# schematic.net
KiCad netlist of a schematic drawn in EAGLE
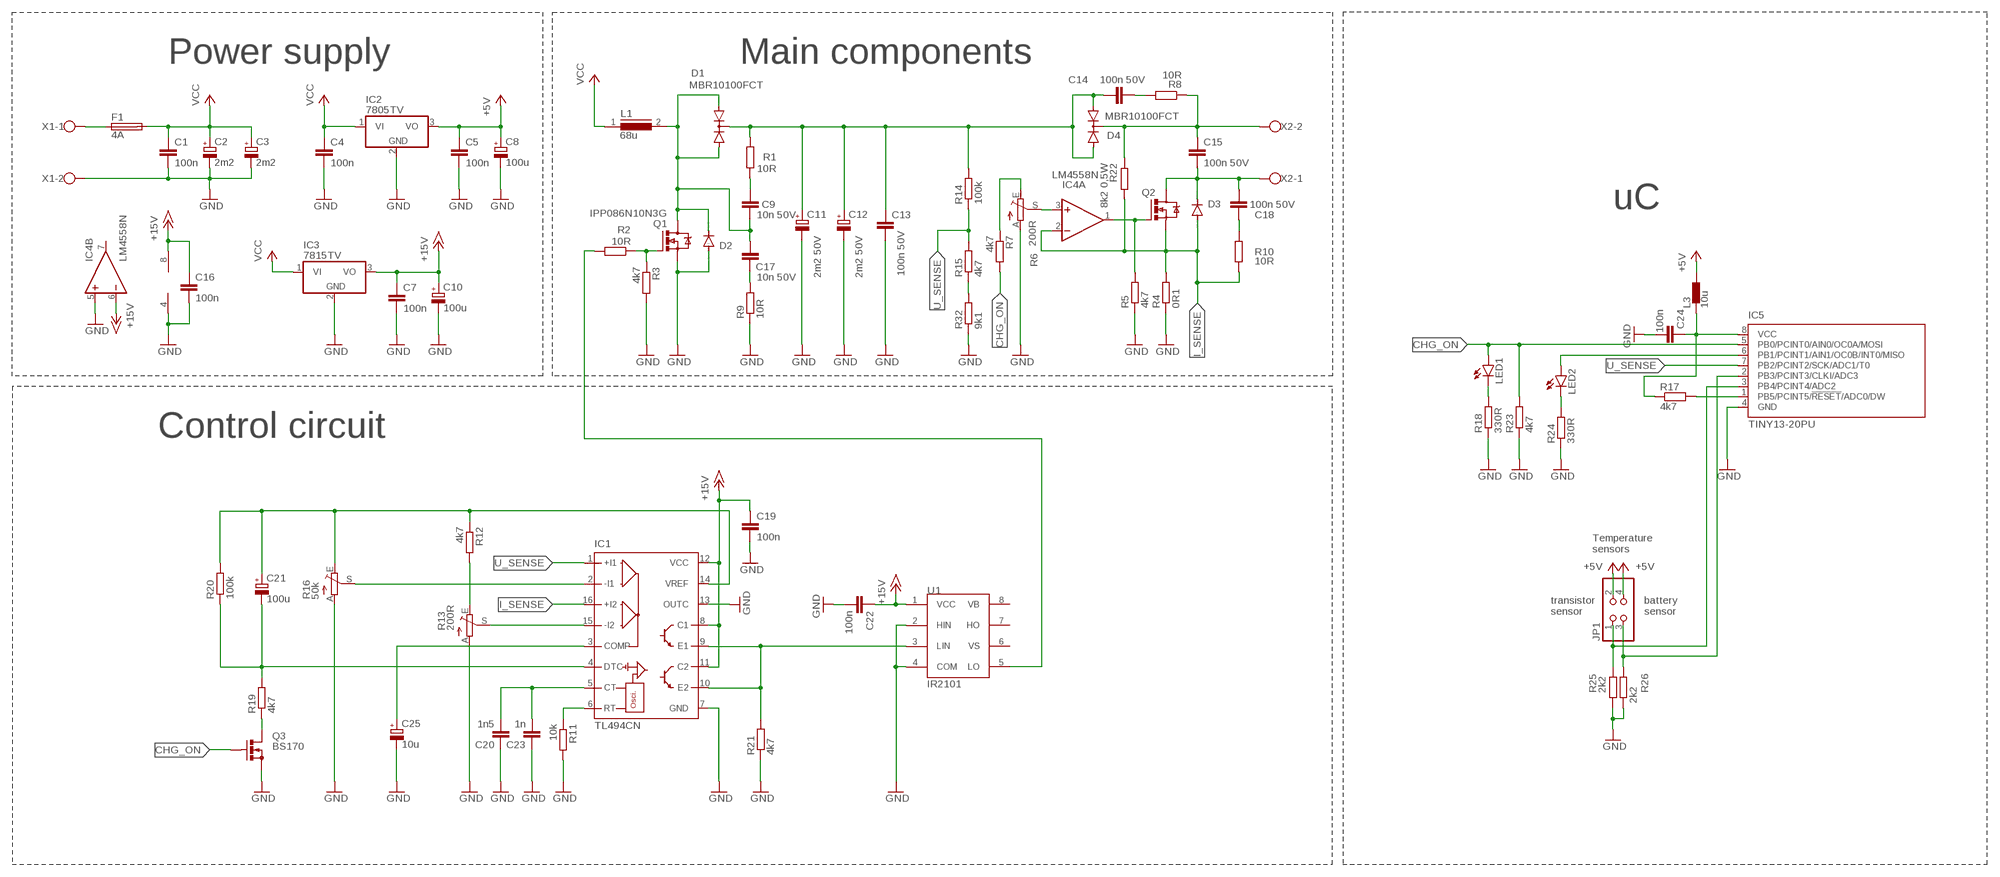
[diagram p0: schematic, sheet 1]

(export (version "E")
  (design (tool "Eeschema 10.0.6"))
  (components
    (comp (ref "C1")
      (value "100n")
      (footprint "eagle-import:C2.5-2")
      (libsource (lib "eagle-import") (part "C2.5/2"))
    )
    (comp (ref "C2")
      (value "2m2")
      (footprint "eagle-import:E7,5-16")
      (libsource (lib "eagle-import") (part "CPOL-EUE7.5-16"))
    )
    (comp (ref "C3")
      (value "2m2")
      (footprint "eagle-import:E7,5-16")
      (libsource (lib "eagle-import") (part "CPOL-EUE7.5-16"))
    )
    (comp (ref "C4")
      (value "100n")
      (footprint "eagle-import:C2.5-2")
      (libsource (lib "eagle-import") (part "C2.5/2"))
    )
    (comp (ref "C5")
      (value "100n")
      (footprint "eagle-import:C2.5-2")
      (libsource (lib "eagle-import") (part "C2.5/2"))
    )
    (comp (ref "C7")
      (value "100n")
      (footprint "eagle-import:C2.5-2")
      (libsource (lib "eagle-import") (part "C2.5/2"))
    )
    (comp (ref "C8")
      (value "100u")
      (footprint "eagle-import:E3,5-8")
      (libsource (lib "eagle-import") (part "CPOL-EUE3.5-8"))
    )
    (comp (ref "C9")
      (value "10n 50V")
      (footprint "eagle-import:C2.5-2")
      (libsource (lib "eagle-import") (part "C2.5/2"))
    )
    (comp (ref "C10")
      (value "100u")
      (footprint "eagle-import:E3,5-8")
      (libsource (lib "eagle-import") (part "CPOL-EUE3.5-8"))
    )
    (comp (ref "C11")
      (value "2m2 50V")
      (footprint "eagle-import:E7,5-18")
      (libsource (lib "eagle-import") (part "CPOL-EUE7.5-18"))
    )
    (comp (ref "C12")
      (value "2m2 50V")
      (footprint "eagle-import:E7,5-18")
      (libsource (lib "eagle-import") (part "CPOL-EUE7.5-18"))
    )
    (comp (ref "C13")
      (value "100n 50V")
      (footprint "eagle-import:C2.5-2")
      (libsource (lib "eagle-import") (part "C2.5/2"))
    )
    (comp (ref "C14")
      (value "100n 50V")
      (footprint "eagle-import:C2.5-2")
      (libsource (lib "eagle-import") (part "C2.5/2"))
    )
    (comp (ref "C15")
      (value "100n 50V")
      (footprint "eagle-import:C2.5-2")
      (libsource (lib "eagle-import") (part "C2.5/2"))
    )
    (comp (ref "C16")
      (value "100n")
      (footprint "eagle-import:C2.5-2")
      (libsource (lib "eagle-import") (part "C2.5/2"))
    )
    (comp (ref "C17")
      (value "10n 50V")
      (footprint "eagle-import:C2.5-2")
      (libsource (lib "eagle-import") (part "C2.5/2"))
    )
    (comp (ref "C18")
      (value "100n 50V")
      (footprint "eagle-import:C2.5-2")
      (libsource (lib "eagle-import") (part "C2.5/2"))
    )
    (comp (ref "C19")
      (value "100n")
      (footprint "eagle-import:C2.5-2")
      (libsource (lib "eagle-import") (part "C2.5/2"))
    )
    (comp (ref "C20")
      (value "1n5")
      (footprint "eagle-import:C2.5-2")
      (libsource (lib "eagle-import") (part "C2.5/2"))
    )
    (comp (ref "C21")
      (value "100u")
      (footprint "eagle-import:E3,5-8")
      (libsource (lib "eagle-import") (part "CPOL-EUE3.5-8"))
    )
    (comp (ref "C22")
      (value "100n")
      (footprint "eagle-import:C2.5-2")
      (libsource (lib "eagle-import") (part "C2.5/2"))
    )
    (comp (ref "C23")
      (value "1n")
      (footprint "eagle-import:C2.5-2")
      (libsource (lib "eagle-import") (part "C2.5/2"))
    )
    (comp (ref "C24")
      (value "100n")
      (footprint "eagle-import:C2.5-2")
      (libsource (lib "eagle-import") (part "C2.5/2"))
    )
    (comp (ref "C25")
      (value "10u")
      (footprint "eagle-import:E2,5-5")
      (libsource (lib "eagle-import") (part "CPOL-EUE2.5-5"))
    )
    (comp (ref "D1")
      (value "MBR10100FCT")
      (footprint "eagle-import:TO220ABS")
      (libsource (lib "eagle-import") (part "BYV32"))
    )
    (comp (ref "D2")
      (value "1N4933")
      (footprint "eagle-import:DO41-10")
      (libsource (lib "eagle-import") (part "1N4933"))
    )
    (comp (ref "D3")
      (value "1N4933")
      (footprint "eagle-import:DO41-10")
      (libsource (lib "eagle-import") (part "1N4933"))
    )
    (comp (ref "D4")
      (value "MBR10100FCT")
      (footprint "eagle-import:TO220ABS")
      (libsource (lib "eagle-import") (part "BYV32"))
    )
    (comp (ref "F1")
      (value "4A")
      (footprint "eagle-import:SH22")
      (libsource (lib "eagle-import") (part "SH22"))
    )
    (comp (ref "IC1")
      (value "TL494CN")
      (footprint "eagle-import:DIL16")
      (libsource (lib "eagle-import") (part "TL494NC"))
    )
    (comp (ref "IC2")
      (value "7805TV")
      (footprint "eagle-import:TO220V")
      (libsource (lib "eagle-import") (part "78TV05"))
    )
    (comp (ref "IC3")
      (value "7815TV")
      (footprint "eagle-import:TO220V")
      (libsource (lib "eagle-import") (part "78TV15"))
    )
    (comp (ref "IC4")
      (value "LM4558N")
      (footprint "eagle-import:DIL08")
      (libsource (lib "eagle-import") (part "4558NLM"))
    )
    (comp (ref "IC5")
      (value "TINY13-20PU")
      (footprint "eagle-import:DIL08")
      (fields (field (name "MPN") "ATTINY13-20PU"))
      (libsource (lib "eagle-import") (part "TINY13PU-20"))
    )
    (comp (ref "JP1")
      (value "PINHD-2X2")
      (footprint "eagle-import:2X02")
      (libsource (lib "eagle-import") (part "PINHD-2X2"))
    )
    (comp (ref "L1")
      (value "68u")
      (footprint "eagle-import:SFT1240")
      (libsource (lib "eagle-import") (part "SFT1240"))
    )
    (comp (ref "L3")
      (value "10u")
      (footprint "eagle-import:BL01RN1A")
      (libsource (lib "eagle-import") (part "BL01RN1A"))
    )
    (comp (ref "LED1")
      (value "LED5MM")
      (footprint "eagle-import:LED5MM")
      (libsource (lib "eagle-import") (part "LED5MM"))
    )
    (comp (ref "LED2")
      (value "LED5MM")
      (footprint "eagle-import:LED5MM")
      (libsource (lib "eagle-import") (part "LED5MM"))
    )
    (comp (ref "Q1")
      (value "IPP086N10N3G")
      (footprint "eagle-import:TO220BV")
      (libsource (lib "eagle-import") (part "IRF520"))
    )
    (comp (ref "Q2")
      (value "IRF520")
      (footprint "eagle-import:TO220BV")
      (libsource (lib "eagle-import") (part "IRF520"))
    )
    (comp (ref "Q3")
      (value "BS170")
      (footprint "eagle-import:SOT54E")
      (libsource (lib "eagle-import") (part "BS170"))
    )
    (comp (ref "R1")
      (value "10R")
      (footprint "eagle-import:0204_7")
      (libsource (lib "eagle-import") (part "R-EU_0204/7"))
    )
    (comp (ref "R2")
      (value "10R")
      (footprint "eagle-import:0204_7")
      (libsource (lib "eagle-import") (part "R-EU_0204/7"))
    )
    (comp (ref "R3")
      (value "4k7")
      (footprint "eagle-import:0204_7")
      (libsource (lib "eagle-import") (part "R-EU_0204/7"))
    )
    (comp (ref "R4")
      (value "0R1")
      (footprint "eagle-import:0204_5")
      (libsource (lib "eagle-import") (part "R-EU_0204/5"))
    )
    (comp (ref "R5")
      (value "4k7")
      (footprint "eagle-import:0204_7")
      (libsource (lib "eagle-import") (part "R-EU_0204/7"))
    )
    (comp (ref "R6")
      (value "200R")
      (footprint "eagle-import:B64Y")
      (libsource (lib "eagle-import") (part "TRIM_EU-B64Y"))
    )
    (comp (ref "R7")
      (value "4k7")
      (footprint "eagle-import:0204_7")
      (libsource (lib "eagle-import") (part "R-EU_0204/7"))
    )
    (comp (ref "R8")
      (value "10R")
      (footprint "eagle-import:0204_7")
      (libsource (lib "eagle-import") (part "R-EU_0204/7"))
    )
    (comp (ref "R9")
      (value "10R")
      (footprint "eagle-import:0204_7")
      (libsource (lib "eagle-import") (part "R-EU_0204/7"))
    )
    (comp (ref "R10")
      (value "10R")
      (footprint "eagle-import:0204_7")
      (libsource (lib "eagle-import") (part "R-EU_0204/7"))
    )
    (comp (ref "R11")
      (value "10k")
      (footprint "eagle-import:0204_7")
      (libsource (lib "eagle-import") (part "R-EU_0204/7"))
    )
    (comp (ref "R12")
      (value "4k7")
      (footprint "eagle-import:0204_7")
      (libsource (lib "eagle-import") (part "R-EU_0204/7"))
    )
    (comp (ref "R13")
      (value "200R")
      (footprint "eagle-import:B64Y")
      (libsource (lib "eagle-import") (part "TRIM_EU-B64Y"))
    )
    (comp (ref "R14")
      (value "100k")
      (footprint "eagle-import:0204_7")
      (libsource (lib "eagle-import") (part "R-EU_0204/7"))
    )
    (comp (ref "R15")
      (value "4k7")
      (footprint "eagle-import:0204_7")
      (libsource (lib "eagle-import") (part "R-EU_0204/7"))
    )
    (comp (ref "R16")
      (value "50k")
      (footprint "eagle-import:B64W")
      (libsource (lib "eagle-import") (part "TRIM_EU-B64W"))
    )
    (comp (ref "R17")
      (value "4k7")
      (footprint "eagle-import:0204_7")
      (libsource (lib "eagle-import") (part "R-EU_0204/7"))
    )
    (comp (ref "R18")
      (value "330R")
      (footprint "eagle-import:0204_7")
      (libsource (lib "eagle-import") (part "R-EU_0204/7"))
    )
    (comp (ref "R19")
      (value "4k7")
      (footprint "eagle-import:0204_7")
      (libsource (lib "eagle-import") (part "R-EU_0204/7"))
    )
    (comp (ref "R20")
      (value "100k")
      (footprint "eagle-import:0204_7")
      (libsource (lib "eagle-import") (part "R-EU_0204/7"))
    )
    (comp (ref "R21")
      (value "4k7")
      (footprint "eagle-import:0204_7")
      (libsource (lib "eagle-import") (part "R-EU_0204/7"))
    )
    (comp (ref "R22")
      (value "8k2 0,5W")
      (footprint "eagle-import:0204_7")
      (libsource (lib "eagle-import") (part "R-EU_0204/7"))
    )
    (comp (ref "R23")
      (value "4k7")
      (footprint "eagle-import:0204_7")
      (libsource (lib "eagle-import") (part "R-EU_0204/7"))
    )
    (comp (ref "R24")
      (value "330R")
      (footprint "eagle-import:0204_7")
      (libsource (lib "eagle-import") (part "R-EU_0204/7"))
    )
    (comp (ref "R25")
      (value "2k2")
      (footprint "eagle-import:0204_7")
      (libsource (lib "eagle-import") (part "R-EU_0204/7"))
    )
    (comp (ref "R26")
      (value "2k2")
      (footprint "eagle-import:0204_7")
      (libsource (lib "eagle-import") (part "R-EU_0204/7"))
    )
    (comp (ref "R32")
      (value "9k1")
      (footprint "eagle-import:0204_7")
      (libsource (lib "eagle-import") (part "R-EU_0204/7"))
    )
    (comp (ref "U1")
      (value "IR2101")
      (footprint "eagle-import:DIL08")
      (libsource (lib "eagle-import") (part "IR2101"))
    )
    (comp (ref "X1")
      (value "W237-102")
      (footprint "eagle-import:W237-102")
      (fields (field (name "MPN") "237-102"))
      (libsource (lib "eagle-import") (part "W237-102"))
    )
    (comp (ref "X2")
      (value "W237-102")
      (footprint "eagle-import:W237-102")
      (fields (field (name "MPN") "237-102"))
      (libsource (lib "eagle-import") (part "W237-102"))
    )
  )
  (nets
    (net (code "1") (name "+5V") (class "Default")
      (node (ref "C5") (pin "1") (pinfunction "1_1") (pintype "passive"))
      (node (ref "C8") (pin "+") (pinfunction "+_+") (pintype "passive"))
      (node (ref "IC2") (pin "3") (pinfunction "VO_3") (pintype "passive"))
      (node (ref "JP1") (pin "2") (pinfunction "2_2") (pintype "passive"))
      (node (ref "JP1") (pin "4") (pinfunction "4_4") (pintype "passive"))
      (node (ref "L3") (pin "2") (pinfunction "2_2") (pintype "passive"))
    )
    (net (code "2") (name "+15V") (class "Default")
      (node (ref "C10") (pin "+") (pinfunction "+_+") (pintype "passive"))
      (node (ref "C16") (pin "1") (pinfunction "1_1") (pintype "passive"))
      (node (ref "C19") (pin "1") (pinfunction "1_1") (pintype "passive"))
      (node (ref "C22") (pin "1") (pinfunction "1_1") (pintype "passive"))
      (node (ref "C7") (pin "1") (pinfunction "1_1") (pintype "passive"))
      (node (ref "IC1") (pin "11") (pinfunction "C2_11") (pintype "passive"))
      (node (ref "IC1") (pin "12") (pinfunction "VCC_12") (pintype "power_in"))
      (node (ref "IC1") (pin "8") (pinfunction "C1_8") (pintype "passive"))
      (node (ref "IC3") (pin "3") (pinfunction "VO_3") (pintype "passive"))
      (node (ref "IC4") (pin "6") (pinfunction "-IN_6") (pintype "input"))
      (node (ref "IC4") (pin "8") (pinfunction "V+_8") (pintype "power_in"))
      (node (ref "U1") (pin "1") (pinfunction "VCC_1") (pintype "power_in"))
    )
    (net (code "3") (name "/VB") (class "Default")
      (node (ref "U1") (pin "8") (pinfunction "VB_8") (pintype "power_in"))
    )
    (net (code "4") (name "CHG_ON") (class "Default")
      (node (ref "IC5") (pin "5") (pinfunction "PB0/PCINT0/AIN0/OC0A/MOSI_5") (pintype "bidirectional"))
      (node (ref "LED1") (pin "A") (pinfunction "A_A") (pintype "passive"))
      (node (ref "Q3") (pin "G") (pinfunction "G_G") (pintype "passive"))
      (node (ref "R23") (pin "2") (pinfunction "2_2") (pintype "passive"))
      (node (ref "R7") (pin "2") (pinfunction "2_2") (pintype "passive"))
    )
    (net (code "5") (name "GND") (class "Default")
      (node (ref "C1") (pin "2") (pinfunction "2_2") (pintype "passive"))
      (node (ref "C10") (pin "-") (pinfunction "-_-") (pintype "passive"))
      (node (ref "C11") (pin "-") (pinfunction "-_-") (pintype "passive"))
      (node (ref "C12") (pin "-") (pinfunction "-_-") (pintype "passive"))
      (node (ref "C13") (pin "2") (pinfunction "2_2") (pintype "passive"))
      (node (ref "C16") (pin "2") (pinfunction "2_2") (pintype "passive"))
      (node (ref "C19") (pin "2") (pinfunction "2_2") (pintype "passive"))
      (node (ref "C2") (pin "-") (pinfunction "-_-") (pintype "passive"))
      (node (ref "C20") (pin "1") (pinfunction "1_1") (pintype "passive"))
      (node (ref "C22") (pin "2") (pinfunction "2_2") (pintype "passive"))
      (node (ref "C23") (pin "1") (pinfunction "1_1") (pintype "passive"))
      (node (ref "C24") (pin "2") (pinfunction "2_2") (pintype "passive"))
      (node (ref "C25") (pin "-") (pinfunction "-_-") (pintype "passive"))
      (node (ref "C3") (pin "-") (pinfunction "-_-") (pintype "passive"))
      (node (ref "C4") (pin "2") (pinfunction "2_2") (pintype "passive"))
      (node (ref "C5") (pin "2") (pinfunction "2_2") (pintype "passive"))
      (node (ref "C7") (pin "2") (pinfunction "2_2") (pintype "passive"))
      (node (ref "C8") (pin "-") (pinfunction "-_-") (pintype "passive"))
      (node (ref "D2") (pin "A") (pinfunction "A_A") (pintype "passive"))
      (node (ref "IC1") (pin "13") (pinfunction "OUTC_13") (pintype "output"))
      (node (ref "IC1") (pin "7") (pinfunction "GND_7") (pintype "power_in"))
      (node (ref "IC2") (pin "2") (pinfunction "GND_2") (pintype "passive"))
      (node (ref "IC3") (pin "2") (pinfunction "GND_2") (pintype "passive"))
      (node (ref "IC4") (pin "4") (pinfunction "V-_4") (pintype "power_in"))
      (node (ref "IC4") (pin "5") (pinfunction "+IN_5") (pintype "input"))
      (node (ref "IC5") (pin "4") (pinfunction "GND_4") (pintype "power_in"))
      (node (ref "Q1") (pin "S") (pinfunction "S_S") (pintype "passive"))
      (node (ref "Q3") (pin "S") (pinfunction "S_S") (pintype "passive"))
      (node (ref "R11") (pin "2") (pinfunction "2_2") (pintype "passive"))
      (node (ref "R13") (pin "A") (pinfunction "A_A") (pintype "passive"))
      (node (ref "R16") (pin "A") (pinfunction "A_A") (pintype "passive"))
      (node (ref "R18") (pin "1") (pinfunction "1_1") (pintype "passive"))
      (node (ref "R21") (pin "1") (pinfunction "1_1") (pintype "passive"))
      (node (ref "R23") (pin "1") (pinfunction "1_1") (pintype "passive"))
      (node (ref "R24") (pin "1") (pinfunction "1_1") (pintype "passive"))
      (node (ref "R25") (pin "1") (pinfunction "1_1") (pintype "passive"))
      (node (ref "R26") (pin "1") (pinfunction "1_1") (pintype "passive"))
      (node (ref "R3") (pin "2") (pinfunction "2_2") (pintype "passive"))
      (node (ref "R32") (pin "1") (pinfunction "1_1") (pintype "passive"))
      (node (ref "R4") (pin "1") (pinfunction "1_1") (pintype "passive"))
      (node (ref "R5") (pin "1") (pinfunction "1_1") (pintype "passive"))
      (node (ref "R6") (pin "A") (pinfunction "A_A") (pintype "passive"))
      (node (ref "R9") (pin "1") (pinfunction "1_1") (pintype "passive"))
      (node (ref "U1") (pin "2") (pinfunction "HIN_2") (pintype "input"))
      (node (ref "U1") (pin "4") (pinfunction "COM_4") (pintype "power_in"))
      (node (ref "X1") (pin "2") (pinfunction "KL_2") (pintype "passive"))
    )
    (net (code "6") (name "I_SENSE") (class "Default")
      (node (ref "D3") (pin "A") (pinfunction "A_A") (pintype "passive"))
      (node (ref "IC1") (pin "16") (pinfunction "+I2_16") (pintype "input"))
      (node (ref "IC4") (pin "2") (pinfunction "-IN_2") (pintype "input"))
      (node (ref "Q2") (pin "S") (pinfunction "S_S") (pintype "passive"))
      (node (ref "R10") (pin "2") (pinfunction "2_2") (pintype "passive"))
      (node (ref "R22") (pin "2") (pinfunction "2_2") (pintype "passive"))
      (node (ref "R4") (pin "2") (pinfunction "2_2") (pintype "passive"))
    )
    (net (code "7") (name "Net-(C9-Pad1)") (class "Default")
      (node (ref "C9") (pin "1") (pinfunction "1_1") (pintype "passive"))
      (node (ref "R1") (pin "1") (pinfunction "1_1") (pintype "passive"))
    )
    (net (code "8") (name "Net-(C11-Pad+)") (class "Default")
      (node (ref "C11") (pin "+") (pinfunction "+_+") (pintype "passive"))
      (node (ref "C12") (pin "+") (pinfunction "+_+") (pintype "passive"))
      (node (ref "C13") (pin "1") (pinfunction "1_1") (pintype "passive"))
      (node (ref "C14") (pin "2") (pinfunction "2_2") (pintype "passive"))
      (node (ref "D1") (pin "C") (pinfunction "C_C") (pintype "passive"))
      (node (ref "D4") (pin "A1") (pinfunction "A1_A1") (pintype "passive"))
      (node (ref "D4") (pin "A2") (pinfunction "A2_A2") (pintype "passive"))
      (node (ref "R1") (pin "2") (pinfunction "2_2") (pintype "passive"))
      (node (ref "R14") (pin "2") (pinfunction "2_2") (pintype "passive"))
    )
    (net (code "9") (name "Net-(C14-Pad1)") (class "Default")
      (node (ref "C14") (pin "1") (pinfunction "1_1") (pintype "passive"))
      (node (ref "R8") (pin "2") (pinfunction "2_2") (pintype "passive"))
    )
    (net (code "10") (name "Net-(C17-Pad1)") (class "Default")
      (node (ref "C17") (pin "1") (pinfunction "1_1") (pintype "passive"))
      (node (ref "C9") (pin "2") (pinfunction "2_2") (pintype "passive"))
      (node (ref "D1") (pin "A1") (pinfunction "A1_A1") (pintype "passive"))
      (node (ref "D1") (pin "A2") (pinfunction "A2_A2") (pintype "passive"))
      (node (ref "D2") (pin "C") (pinfunction "C_C") (pintype "passive"))
      (node (ref "L1") (pin "2") (pinfunction "2_2") (pintype "passive"))
      (node (ref "Q1") (pin "D") (pinfunction "D_D") (pintype "passive"))
    )
    (net (code "11") (name "Net-(C17-Pad2)") (class "Default")
      (node (ref "C17") (pin "2") (pinfunction "2_2") (pintype "passive"))
      (node (ref "R9") (pin "2") (pinfunction "2_2") (pintype "passive"))
    )
    (net (code "12") (name "Net-(C18-Pad2)") (class "Default")
      (node (ref "C18") (pin "2") (pinfunction "2_2") (pintype "passive"))
      (node (ref "R10") (pin "1") (pinfunction "1_1") (pintype "passive"))
    )
    (net (code "13") (name "Net-(IC1--I1)") (class "Default")
      (node (ref "IC1") (pin "2") (pinfunction "-I1_2") (pintype "input"))
      (node (ref "R16") (pin "S") (pinfunction "S_S") (pintype "passive"))
    )
    (net (code "14") (name "Net-(IC1--I2)") (class "Default")
      (node (ref "IC1") (pin "15") (pinfunction "-I2_15") (pintype "input"))
      (node (ref "R13") (pin "S") (pinfunction "S_S") (pintype "passive"))
    )
    (net (code "15") (name "Net-(IC1-COMP)") (class "Default")
      (node (ref "C25") (pin "+") (pinfunction "+_+") (pintype "passive"))
      (node (ref "IC1") (pin "3") (pinfunction "COMP_3") (pintype "passive"))
    )
    (net (code "16") (name "Net-(IC1-CT)") (class "Default")
      (node (ref "C20") (pin "2") (pinfunction "2_2") (pintype "passive"))
      (node (ref "C23") (pin "2") (pinfunction "2_2") (pintype "passive"))
      (node (ref "IC1") (pin "5") (pinfunction "CT_5") (pintype "input"))
    )
    (net (code "17") (name "Net-(IC1-DTC)") (class "Default")
      (node (ref "C21") (pin "-") (pinfunction "-_-") (pintype "passive"))
      (node (ref "IC1") (pin "4") (pinfunction "DTC_4") (pintype "input"))
      (node (ref "R19") (pin "2") (pinfunction "2_2") (pintype "passive"))
      (node (ref "R20") (pin "1") (pinfunction "1_1") (pintype "passive"))
    )
    (net (code "18") (name "Net-(IC1-E1)") (class "Default")
      (node (ref "IC1") (pin "10") (pinfunction "E2_10") (pintype "passive"))
      (node (ref "IC1") (pin "9") (pinfunction "E1_9") (pintype "passive"))
      (node (ref "R21") (pin "2") (pinfunction "2_2") (pintype "passive"))
      (node (ref "U1") (pin "3") (pinfunction "LIN_3") (pintype "input"))
    )
    (net (code "19") (name "Net-(IC1-RT)") (class "Default")
      (node (ref "IC1") (pin "6") (pinfunction "RT_6") (pintype "input"))
      (node (ref "R11") (pin "1") (pinfunction "1_1") (pintype "passive"))
    )
    (net (code "20") (name "Net-(IC1-VREF)") (class "Default")
      (node (ref "C21") (pin "+") (pinfunction "+_+") (pintype "passive"))
      (node (ref "IC1") (pin "14") (pinfunction "VREF_14") (pintype "input"))
      (node (ref "R12") (pin "1") (pinfunction "1_1") (pintype "passive"))
      (node (ref "R16") (pin "E") (pinfunction "E_E") (pintype "passive"))
      (node (ref "R20") (pin "2") (pinfunction "2_2") (pintype "passive"))
    )
    (net (code "21") (name "Net-(IC4A-+IN)") (class "Default")
      (node (ref "IC4") (pin "3") (pinfunction "+IN_3") (pintype "input"))
      (node (ref "R6") (pin "S") (pinfunction "S_S") (pintype "passive"))
    )
    (net (code "22") (name "Net-(IC4A-OUT)") (class "Default")
      (node (ref "IC4") (pin "1") (pinfunction "OUT_1") (pintype "output"))
      (node (ref "Q2") (pin "G") (pinfunction "G_G") (pintype "passive"))
      (node (ref "R5") (pin "2") (pinfunction "2_2") (pintype "passive"))
    )
    (net (code "23") (name "Net-(IC5-PB1{slash}PCINT1{slash}AIN1{slash}OC0B{slash}INT0{slash}MISO)") (class "Default")
      (node (ref "IC5") (pin "6") (pinfunction "PB1/PCINT1/AIN1/OC0B/INT0/MISO_6") (pintype "bidirectional"))
      (node (ref "LED2") (pin "A") (pinfunction "A_A") (pintype "passive"))
    )
    (net (code "24") (name "Net-(IC5-PB3{slash}PCINT3{slash}CLKI{slash}ADC3)") (class "Default")
      (node (ref "IC5") (pin "2") (pinfunction "PB3/PCINT3/CLKI/ADC3_2") (pintype "bidirectional"))
      (node (ref "JP1") (pin "3") (pinfunction "3_3") (pintype "passive"))
      (node (ref "R26") (pin "2") (pinfunction "2_2") (pintype "passive"))
    )
    (net (code "25") (name "Net-(IC5-PB4{slash}PCINT4{slash}ADC2)") (class "Default")
      (node (ref "IC5") (pin "3") (pinfunction "PB4/PCINT4/ADC2_3") (pintype "bidirectional"))
      (node (ref "JP1") (pin "1") (pinfunction "1_1") (pintype "passive"))
      (node (ref "R25") (pin "2") (pinfunction "2_2") (pintype "passive"))
    )
    (net (code "26") (name "Net-(IC5-PB5{slash}PCINT5{slash}~{RESET}{slash}ADC0{slash}DW)") (class "Default")
      (node (ref "IC5") (pin "1") (pinfunction "PB5/PCINT5/~{RESET}/ADC0/DW_1") (pintype "bidirectional"))
      (node (ref "R17") (pin "2") (pinfunction "2_2") (pintype "passive"))
    )
    (net (code "27") (name "Net-(IC5-VCC)") (class "Default")
      (node (ref "C24") (pin "1") (pinfunction "1_1") (pintype "passive"))
      (node (ref "IC5") (pin "8") (pinfunction "VCC_8") (pintype "power_in"))
      (node (ref "L3") (pin "1") (pinfunction "1_1") (pintype "passive"))
      (node (ref "R17") (pin "1") (pinfunction "1_1") (pintype "passive"))
    )
    (net (code "28") (name "Net-(LED1-C)") (class "Default")
      (node (ref "LED1") (pin "K") (pinfunction "C_K") (pintype "passive"))
      (node (ref "R18") (pin "2") (pinfunction "2_2") (pintype "passive"))
    )
    (net (code "29") (name "Net-(LED2-C)") (class "Default")
      (node (ref "LED2") (pin "K") (pinfunction "C_K") (pintype "passive"))
      (node (ref "R24") (pin "2") (pinfunction "2_2") (pintype "passive"))
    )
    (net (code "30") (name "Net-(Q1-PadG)") (class "Default")
      (node (ref "Q1") (pin "G") (pinfunction "G_G") (pintype "passive"))
      (node (ref "R2") (pin "1") (pinfunction "1_1") (pintype "passive"))
      (node (ref "R3") (pin "1") (pinfunction "1_1") (pintype "passive"))
    )
    (net (code "31") (name "Net-(Q3-PadD)") (class "Default")
      (node (ref "Q3") (pin "D") (pinfunction "D_D") (pintype "passive"))
      (node (ref "R19") (pin "1") (pinfunction "1_1") (pintype "passive"))
    )
    (net (code "32") (name "Net-(R6-PadE)") (class "Default")
      (node (ref "R6") (pin "E") (pinfunction "E_E") (pintype "passive"))
      (node (ref "R7") (pin "1") (pinfunction "1_1") (pintype "passive"))
    )
    (net (code "33") (name "Net-(R12-Pad2)") (class "Default")
      (node (ref "R12") (pin "2") (pinfunction "2_2") (pintype "passive"))
      (node (ref "R13") (pin "E") (pinfunction "E_E") (pintype "passive"))
    )
    (net (code "34") (name "Net-(R15-Pad1)") (class "Default")
      (node (ref "R15") (pin "1") (pinfunction "1_1") (pintype "passive"))
      (node (ref "R32") (pin "2") (pinfunction "2_2") (pintype "passive"))
    )
    (net (code "35") (name "Net-(U1-LO)") (class "Default")
      (node (ref "R2") (pin "2") (pinfunction "2_2") (pintype "passive"))
      (node (ref "U1") (pin "5") (pinfunction "LO_5") (pintype "output"))
    )
    (net (code "36") (name "Net-(X1A-KL)") (class "Default")
      (node (ref "F1") (pin "1") (pinfunction "1_1") (pintype "passive"))
      (node (ref "X1") (pin "1") (pinfunction "KL_1") (pintype "passive"))
    )
    (net (code "37") (name "Net-(X2A-KL)") (class "Default")
      (node (ref "C15") (pin "2") (pinfunction "2_2") (pintype "passive"))
      (node (ref "C18") (pin "1") (pinfunction "1_1") (pintype "passive"))
      (node (ref "D3") (pin "C") (pinfunction "C_C") (pintype "passive"))
      (node (ref "Q2") (pin "D") (pinfunction "D_D") (pintype "passive"))
      (node (ref "X2") (pin "1") (pinfunction "KL_1") (pintype "passive"))
    )
    (net (code "38") (name "Net-(X2B-KL)") (class "Default")
      (node (ref "C15") (pin "1") (pinfunction "1_1") (pintype "passive"))
      (node (ref "D4") (pin "C") (pinfunction "C_C") (pintype "passive"))
      (node (ref "R22") (pin "1") (pinfunction "1_1") (pintype "passive"))
      (node (ref "R8") (pin "1") (pinfunction "1_1") (pintype "passive"))
      (node (ref "X2") (pin "2") (pinfunction "KL_2") (pintype "passive"))
    )
    (net (code "39") (name "U_SENSE") (class "Default")
      (node (ref "IC1") (pin "1") (pinfunction "+I1_1") (pintype "input"))
      (node (ref "IC5") (pin "7") (pinfunction "PB2/PCINT2/SCK/ADC1/T0_7") (pintype "bidirectional"))
      (node (ref "R14") (pin "1") (pinfunction "1_1") (pintype "passive"))
      (node (ref "R15") (pin "2") (pinfunction "2_2") (pintype "passive"))
    )
    (net (code "40") (name "VCC") (class "Default")
      (node (ref "C1") (pin "1") (pinfunction "1_1") (pintype "passive"))
      (node (ref "C2") (pin "+") (pinfunction "+_+") (pintype "passive"))
      (node (ref "C3") (pin "+") (pinfunction "+_+") (pintype "passive"))
      (node (ref "C4") (pin "1") (pinfunction "1_1") (pintype "passive"))
      (node (ref "F1") (pin "2") (pinfunction "2_2") (pintype "passive"))
      (node (ref "IC2") (pin "1") (pinfunction "VI_1") (pintype "input"))
      (node (ref "IC3") (pin "1") (pinfunction "VI_1") (pintype "input"))
      (node (ref "L1") (pin "1") (pinfunction "1_1") (pintype "passive"))
    )
    (net (code "41") (name "unconnected-(IC4B-OUT-Pad7)") (class "Default")
      (node (ref "IC4") (pin "7") (pinfunction "OUT_7") (pintype "output"))
    )
    (net (code "42") (name "unconnected-(U1-HO-Pad7)") (class "Default")
      (node (ref "U1") (pin "7") (pinfunction "HO_7") (pintype "output"))
    )
    (net (code "43") (name "unconnected-(U1-VS-Pad6)") (class "Default")
      (node (ref "U1") (pin "6") (pinfunction "VS_6") (pintype "output"))
    )
  )
)
